# aufsatz_v2_1_lm75.net
KiCad netlist of a schematic drawn in EAGLE
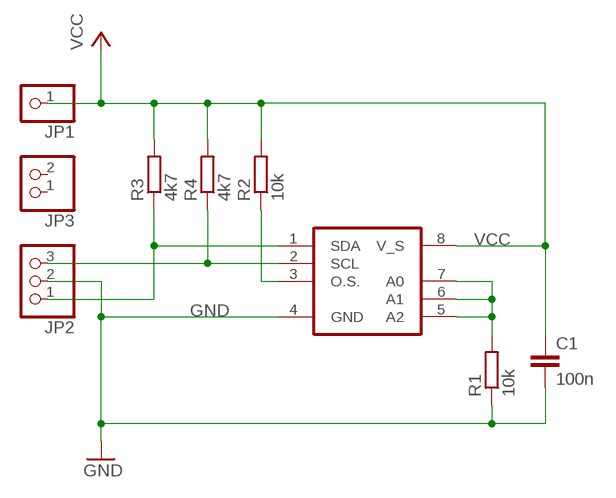
[diagram p0: schematic, sheet 1]

(export (version "E")
  (design (tool "Eeschema 10.0.6"))
  (components
    (comp (ref "C1")
      (value "100n")
      (footprint "eagle-import:C0805")
      (libsource (lib "eagle-import") (part "C-EUC0805"))
    )
    (comp (ref "JP1")
      (value "PINHD-1X1")
      (footprint "eagle-import:1X01")
      (libsource (lib "eagle-import") (part "PINHD-1X1"))
    )
    (comp (ref "JP2")
      (value "PINHD-1X3")
      (footprint "eagle-import:1X03")
      (libsource (lib "eagle-import") (part "PINHD-1X3"))
    )
    (comp (ref "JP3")
      (value "PINHD-1X2")
      (footprint "eagle-import:1X02")
      (libsource (lib "eagle-import") (part "PINHD-1X2"))
    )
    (comp (ref "R1")
      (value "10k")
      (footprint "eagle-import:R0805")
      (libsource (lib "eagle-import") (part "R-EU_R0805"))
    )
    (comp (ref "R2")
      (value "10k")
      (footprint "eagle-import:0204_5")
      (libsource (lib "eagle-import") (part "R-EU_0204/5"))
    )
    (comp (ref "R3")
      (value "4k7")
      (footprint "eagle-import:0204_7")
      (libsource (lib "eagle-import") (part "R-EU_0204/7"))
    )
    (comp (ref "R4")
      (value "4k7")
      (footprint "eagle-import:R0805")
      (libsource (lib "eagle-import") (part "R-EU_R0805"))
    )
    (comp (ref "U$1")
      (value "LM75")
      (footprint "eagle-import:SOIC8")
      (libsource (lib "eagle-import") (part "LM75"))
    )
  )
  (nets
    (net (code "1") (name "GND") (class "Default")
      (node (ref "C1") (pin "2") (pinfunction "2_2") (pintype "passive"))
      (node (ref "JP2") (pin "2") (pinfunction "2_2") (pintype "passive"))
      (node (ref "R1") (pin "1") (pinfunction "1_1") (pintype "passive"))
      (node (ref "U$1") (pin "4") (pinfunction "GND_4") (pintype "power_in"))
    )
    (net (code "2") (name "Net-(U$1-A0)") (class "Default")
      (node (ref "R1") (pin "2") (pinfunction "2_2") (pintype "passive"))
      (node (ref "U$1") (pin "5") (pinfunction "A2_5") (pintype "input"))
      (node (ref "U$1") (pin "6") (pinfunction "A1_6") (pintype "input"))
      (node (ref "U$1") (pin "7") (pinfunction "A0_7") (pintype "input"))
    )
    (net (code "3") (name "Net-(U$1-O.S.)") (class "Default")
      (node (ref "R2") (pin "1") (pinfunction "1_1") (pintype "passive"))
      (node (ref "U$1") (pin "3") (pinfunction "O.S._3") (pintype "open_collector"))
    )
    (net (code "4") (name "Net-(U$1-SCL)") (class "Default")
      (node (ref "JP2") (pin "3") (pinfunction "3_3") (pintype "passive"))
      (node (ref "R4") (pin "1") (pinfunction "1_1") (pintype "passive"))
      (node (ref "U$1") (pin "2") (pinfunction "SCL_2") (pintype "bidirectional"))
    )
    (net (code "5") (name "Net-(U$1-SDA)") (class "Default")
      (node (ref "JP2") (pin "1") (pinfunction "1_1") (pintype "passive"))
      (node (ref "R3") (pin "1") (pinfunction "1_1") (pintype "passive"))
      (node (ref "U$1") (pin "1") (pinfunction "SDA_1") (pintype "bidirectional"))
    )
    (net (code "6") (name "VCC") (class "Default")
      (node (ref "C1") (pin "1") (pinfunction "1_1") (pintype "passive"))
      (node (ref "JP1") (pin "1") (pinfunction "1_1") (pintype "passive"))
      (node (ref "R2") (pin "2") (pinfunction "2_2") (pintype "passive"))
      (node (ref "R3") (pin "2") (pinfunction "2_2") (pintype "passive"))
      (node (ref "R4") (pin "2") (pinfunction "2_2") (pintype "passive"))
      (node (ref "U$1") (pin "8") (pinfunction "V_S_8") (pintype "power_in"))
    )
    (net (code "7") (name "unconnected-(JP3-Pad1)") (class "Default")
      (node (ref "JP3") (pin "1") (pinfunction "1_1") (pintype "passive"))
    )
    (net (code "8") (name "unconnected-(JP3-Pad2)") (class "Default")
      (node (ref "JP3") (pin "2") (pinfunction "2_2") (pintype "passive"))
    )
  )
)
